# nfc.net
KiCad netlist of a schematic drawn in Altium Designer
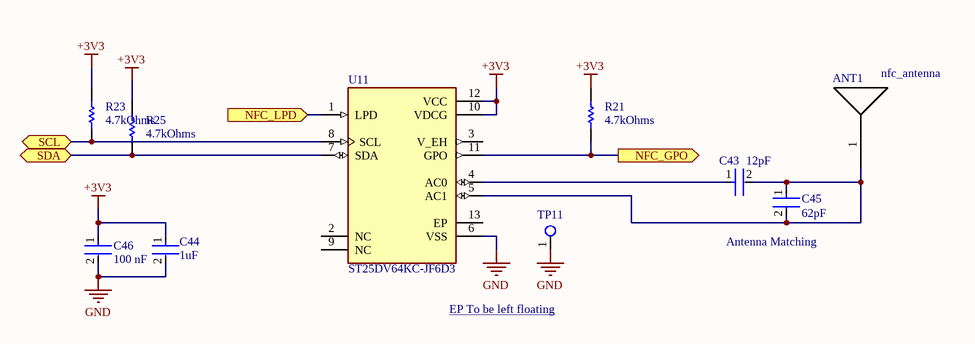
[diagram p0: nfc.SchDoc]

(export (version "E")
  (design (tool "Eeschema 10.0.6"))
  (components
    (comp (ref "ANT1")
      (value "nfc_antenna")
      (footprint "nfc_antenna")
      (libsource (lib "fydp") (part "nfc_antenna"))
    )
    (comp (ref "C43")
      (value "GRM1555C1H120GA01D")
      (footprint "FP-GRM155-0_05-MFG")
      (description "CAP CER 12PF 50V C0G/NP0 0402")
      (fields
        (field (name "TOLERANCE") "2%")
        (field (name "CAPACITANCE") "12pF")
        (field (name "VOLTAGE") "50V")
      )
      (libsource (lib "Altium Content Vault") (part "b4654b650e69147ec39a6b967a45e02"))
    )
    (comp (ref "C44")
      (value "CL10B105KP8NNNC")
      (footprint "FP-CL10-IPC_C")
      (description "Cap Ceramic 1uF 10V X7R ±10% Pad SMD 0603 +125°C T/R")
      (fields (field (name "CAPACITANCE") "1uF") (field (name "TOLERANCE") "10%"))
      (libsource (lib "Altium Content Vault") (part "b4654b650e69147ec39a6b967a45e02"))
    )
    (comp (ref "C45")
      (value "62pF")
      (footprint "FP-GCM155-0_05-IPC_B")
      (description "Ceramic Capacitor for Automotive 62pF ±2% 50VDC C0G 0402 Paper T/R")
      (fields (field (name "Comment") "GCM1555C1H620GA16J"))
      (libsource (lib "Altium Content Vault") (part "02cd4be3c70576c341d710602a673aa"))
    )
    (comp (ref "C46")
      (value "CC0603KRX7R7BB104")
      (footprint "FP-CC0603-DA-MFG")
      (description "CAP CER 0.1UF 16V X7R 0603")
      (fields
        (field (name "OCTOPART") "https://octopart.com/cc0603krx7r7bb104-yageo-192941")
        (field (name "TOLERANCE") "0.1")
        (field (name "CAPACITANCE") "100 nF")
      )
      (libsource (lib "Altium Content Vault") (part "11868f565c42a9108669ba33697ecf6"))
    )
    (comp (ref "R21")
      (value "RC0603FR-074K7L")
      (footprint "RESC1608X55X25LL10T15")
      (description "Chip Resistor, 4.7 KOhm, +/- 1%, 0.1 W, -55 to 155 degC, 0603 (1608 Metric), RoHS, Tape and Reel")
      (fields
        (field (name "MANUFACTURER") "Yageo")
        (field (name "RESISTANCE") "4.7kOhms")
        (field (name "TOLERANCE") "1%")
      )
      (libsource (lib "Altium Content Vault") (part "RES-2"))
    )
    (comp (ref "R23")
      (value "RC0603FR-074K7L")
      (footprint "RESC1608X55X25LL10T15")
      (description "Chip Resistor, 4.7 KOhm, +/- 1%, 0.1 W, -55 to 155 degC, 0603 (1608 Metric), RoHS, Tape and Reel")
      (fields
        (field (name "MANUFACTURER") "Yageo")
        (field (name "RESISTANCE") "4.7kOhms")
        (field (name "TOLERANCE") "1%")
      )
      (libsource (lib "Altium Content Vault") (part "RES-2"))
    )
    (comp (ref "R25")
      (value "RC0603FR-074K7L")
      (footprint "RESC1608X55X25LL10T15")
      (description "Chip Resistor, 4.7 KOhm, +/- 1%, 0.1 W, -55 to 155 degC, 0603 (1608 Metric), RoHS, Tape and Reel")
      (fields
        (field (name "MANUFACTURER") "Yageo")
        (field (name "RESISTANCE") "4.7kOhms")
        (field (name "TOLERANCE") "1%")
      )
      (libsource (lib "Altium Content Vault") (part "RES-2"))
    )
    (comp (ref "TP11")
      (value "Test Point")
      (footprint "test_point")
      (libsource (lib "fydp") (part "Test Point"))
    )
    (comp (ref "U11")
      (value "ST25DV64KC-JF6D3")
      (footprint "PSON50P300X300X60-13N")
      (libsource (lib "fydp") (part "ST25DV64KC-JF6D3"))
    )
  )
  (nets
    (net (code "1") (name "+3V3") (class "Default")
      (node (ref "C44") (pin "1") (pinfunction "1_1") (pintype "passive"))
      (node (ref "C46") (pin "1") (pinfunction "1_1") (pintype "passive"))
      (node (ref "R21") (pin "2") (pinfunction "2_2") (pintype "passive"))
      (node (ref "R23") (pin "2") (pinfunction "2_2") (pintype "passive"))
      (node (ref "R25") (pin "2") (pinfunction "2_2") (pintype "passive"))
      (node (ref "U11") (pin "10") (pinfunction "VDCG_10") (pintype "power_in"))
      (node (ref "U11") (pin "12") (pinfunction "VCC_12") (pintype "power_in"))
    )
    (net (code "2") (name "/NFC_GPO") (class "Default")
      (node (ref "R21") (pin "1") (pinfunction "1_1") (pintype "passive"))
      (node (ref "U11") (pin "11") (pinfunction "GPO_11") (pintype "output"))
    )
    (net (code "3") (name "/NFC_LPD") (class "Default")
      (node (ref "U11") (pin "1") (pinfunction "LPD_1") (pintype "input"))
    )
    (net (code "4") (name "/SCL") (class "Default")
      (node (ref "R23") (pin "1") (pinfunction "1_1") (pintype "passive"))
      (node (ref "U11") (pin "8") (pinfunction "SCL_8") (pintype "input"))
    )
    (net (code "5") (name "/SDA") (class "Default")
      (node (ref "R25") (pin "1") (pinfunction "1_1") (pintype "passive"))
      (node (ref "U11") (pin "7") (pinfunction "SDA_7") (pintype "bidirectional"))
    )
    (net (code "6") (name "GND") (class "Default")
      (node (ref "C44") (pin "2") (pinfunction "2_2") (pintype "passive"))
      (node (ref "C46") (pin "2") (pinfunction "2_2") (pintype "passive"))
      (node (ref "TP11") (pin "1") (pintype "passive"))
      (node (ref "U11") (pin "6") (pinfunction "VSS_6") (pintype "power_in"))
    )
    (net (code "7") (name "Net-(U11-AC0)") (class "Default")
      (node (ref "C43") (pin "1") (pinfunction "1_1") (pintype "passive"))
      (node (ref "U11") (pin "4") (pinfunction "AC0_4") (pintype "bidirectional"))
    )
    (net (code "8") (name "Net-(U11-AC1)") (class "Default")
      (node (ref "ANT1") (pin "1") (pinfunction "1_1") (pintype "passive"))
      (node (ref "C43") (pin "2") (pinfunction "2_2") (pintype "passive"))
      (node (ref "C45") (pin "1") (pinfunction "1_1") (pintype "passive"))
      (node (ref "C45") (pin "2") (pinfunction "2_2") (pintype "passive"))
      (node (ref "U11") (pin "5") (pinfunction "AC1_5") (pintype "bidirectional"))
    )
    (net (code "9") (name "unconnected-(U11-EP-Pad13)") (class "Default")
      (node (ref "U11") (pin "13") (pinfunction "EP_13") (pintype "passive"))
    )
    (net (code "10") (name "unconnected-(U11-NC-Pad2)") (class "Default")
      (node (ref "U11") (pin "2") (pinfunction "NC_2") (pintype "passive"))
    )
    (net (code "11") (name "unconnected-(U11-NC-Pad9)") (class "Default")
      (node (ref "U11") (pin "9") (pinfunction "NC_9") (pintype "passive"))
    )
    (net (code "12") (name "unconnected-(U11-V_EH-Pad3)") (class "Default")
      (node (ref "U11") (pin "3") (pinfunction "V_EH_3") (pintype "output"))
    )
  )
)
